# USB_Type_C_Connector_ESD.net
KiCad netlist of a schematic drawn in Altium Designer
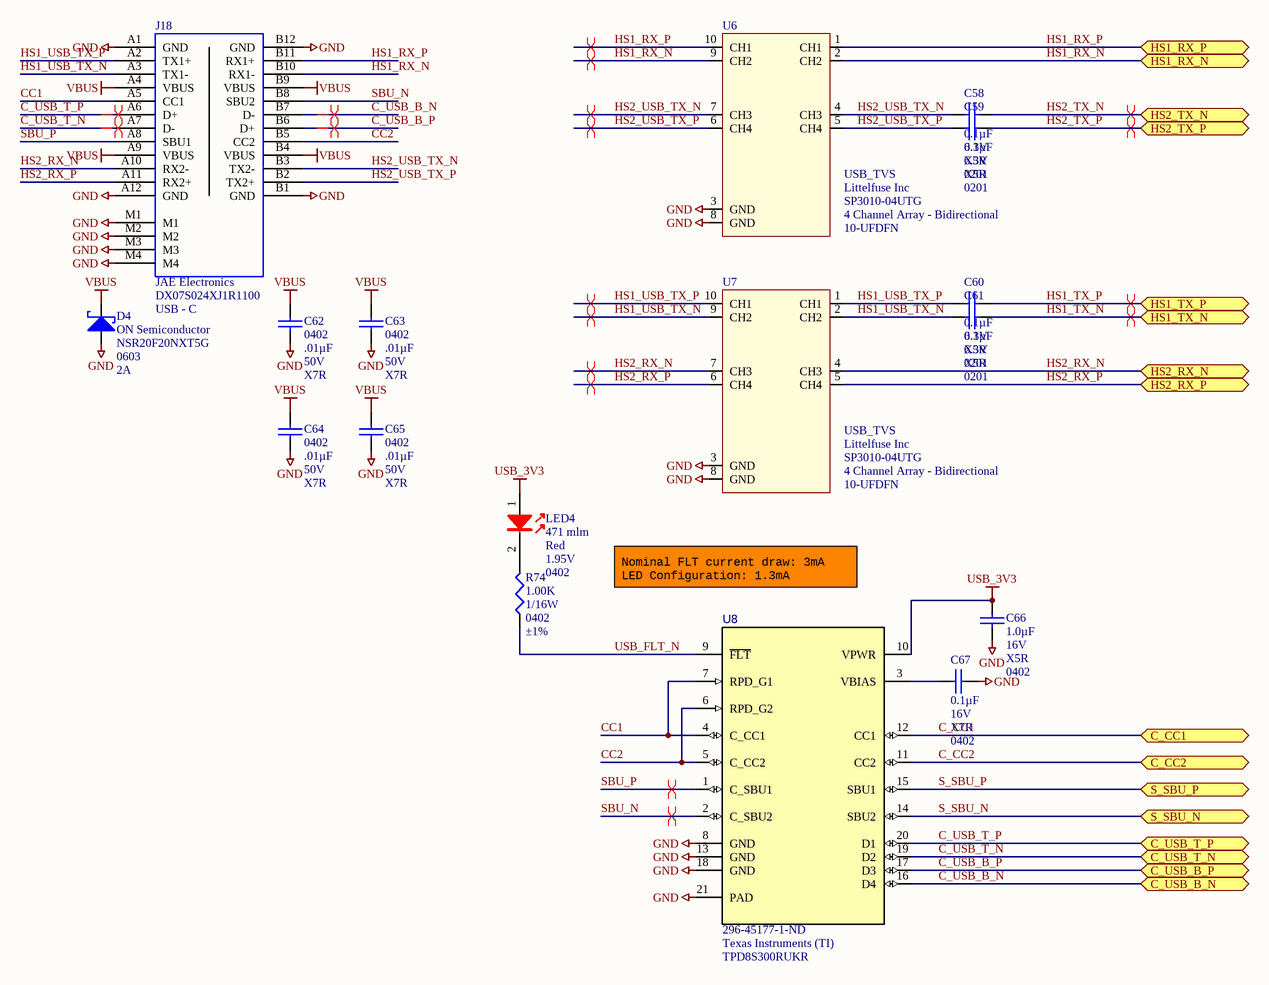
[diagram p0: USB Type C Connector ESD.SchDoc]

(export (version "E")
  (design (tool "Eeschema 10.0.6"))
  (components
    (comp (ref "C58")
      (value "0.1UF")
      (footprint "CAPC0201")
      (description "CAP CER 0.1UF 6.3V 10% X5R 0201")
      (fields
        (field (name "MANUFACTURER") "Murata Electronics North America")
        (field (name "MANUFACTURER PART NUMBER") "GRM033R60J104KE19D")
        (field (name "CAPACITANCE") "0.1µF")
        (field (name "VOLTAGE - RATED") "6.3V")
        (field (name "TEMPERATURE COEFFICIENT") "X5R")
        (field (name "PACKAGE / CASE") "0201")
      )
      (libsource (lib "Main LibraryX") (part "C_0201_0.1UF"))
    )
    (comp (ref "C59")
      (value "0.1UF")
      (footprint "CAPC0201")
      (description "CAP CER 0.1UF 6.3V 10% X5R 0201")
      (fields
        (field (name "MANUFACTURER") "Murata Electronics North America")
        (field (name "MANUFACTURER PART NUMBER") "GRM033R60J104KE19D")
        (field (name "CAPACITANCE") "0.1µF")
        (field (name "VOLTAGE - RATED") "6.3V")
        (field (name "TEMPERATURE COEFFICIENT") "X5R")
        (field (name "PACKAGE / CASE") "0201")
      )
      (libsource (lib "Main LibraryX") (part "C_0201_0.1UF"))
    )
    (comp (ref "C60")
      (value "0.1UF")
      (footprint "CAPC0201")
      (description "CAP CER 0.1UF 6.3V 10% X5R 0201")
      (fields
        (field (name "MANUFACTURER") "Murata Electronics North America")
        (field (name "MANUFACTURER PART NUMBER") "GRM033R60J104KE19D")
        (field (name "CAPACITANCE") "0.1µF")
        (field (name "VOLTAGE - RATED") "6.3V")
        (field (name "TEMPERATURE COEFFICIENT") "X5R")
        (field (name "PACKAGE / CASE") "0201")
      )
      (libsource (lib "Main LibraryX") (part "C_0201_0.1UF"))
    )
    (comp (ref "C61")
      (value "0.1UF")
      (footprint "CAPC0201")
      (description "CAP CER 0.1UF 6.3V 10% X5R 0201")
      (fields
        (field (name "MANUFACTURER") "Murata Electronics North America")
        (field (name "MANUFACTURER PART NUMBER") "GRM033R60J104KE19D")
        (field (name "CAPACITANCE") "0.1µF")
        (field (name "VOLTAGE - RATED") "6.3V")
        (field (name "TEMPERATURE COEFFICIENT") "X5R")
        (field (name "PACKAGE / CASE") "0201")
      )
      (libsource (lib "Main LibraryX") (part "C_0201_0.1UF"))
    )
    (comp (ref "C62")
      (value "10000pF")
      (footprint "C_0402")
      (description "CAP CERAMIC .01UF 50V X7R 0402")
      (fields
        (field (name "MANUFACTURER") "Murata Electronics North America")
        (field (name "MANUFACTURER PART NUMBER") "GRM155R71H103KA88D")
        (field (name "PACKAGE / CASE") "0402")
        (field (name "CAPACITANCE") ".01µF")
        (field (name "VOLTAGE - RATED") "50V")
        (field (name "TEMPERATURE COEFFICIENT") "X7R")
      )
      (libsource (lib "Main Library") (part "C_0402_10000PF_50V"))
    )
    (comp (ref "C63")
      (value "10000pF")
      (footprint "C_0402")
      (description "CAP CERAMIC .01UF 50V X7R 0402")
      (fields
        (field (name "MANUFACTURER") "Murata Electronics North America")
        (field (name "MANUFACTURER PART NUMBER") "GRM155R71H103KA88D")
        (field (name "PACKAGE / CASE") "0402")
        (field (name "CAPACITANCE") ".01µF")
        (field (name "VOLTAGE - RATED") "50V")
        (field (name "TEMPERATURE COEFFICIENT") "X7R")
      )
      (libsource (lib "Main Library") (part "C_0402_10000PF_50V"))
    )
    (comp (ref "C64")
      (value "10000pF")
      (footprint "C_0402")
      (description "CAP CERAMIC .01UF 50V X7R 0402")
      (fields
        (field (name "MANUFACTURER") "Murata Electronics North America")
        (field (name "MANUFACTURER PART NUMBER") "GRM155R71H103KA88D")
        (field (name "PACKAGE / CASE") "0402")
        (field (name "CAPACITANCE") ".01µF")
        (field (name "VOLTAGE - RATED") "50V")
        (field (name "TEMPERATURE COEFFICIENT") "X7R")
      )
      (libsource (lib "Main Library") (part "C_0402_10000PF_50V"))
    )
    (comp (ref "C65")
      (value "10000pF")
      (footprint "C_0402")
      (description "CAP CERAMIC .01UF 50V X7R 0402")
      (fields
        (field (name "MANUFACTURER") "Murata Electronics North America")
        (field (name "MANUFACTURER PART NUMBER") "GRM155R71H103KA88D")
        (field (name "PACKAGE / CASE") "0402")
        (field (name "CAPACITANCE") ".01µF")
        (field (name "VOLTAGE - RATED") "50V")
        (field (name "TEMPERATURE COEFFICIENT") "X7R")
      )
      (libsource (lib "Main Library") (part "C_0402_10000PF_50V"))
    )
    (comp (ref "C66")
      (value "1.0uF")
      (footprint "C_ERA-0402")
      (description "CAP CER 1.0UF 16V X5R 0402")
      (fields
        (field (name "MANUFACTURER") "Taiyo Yuden")
        (field (name "MANUFACTURER PART NUMBER") "EMK105BJ105KV-F")
        (field (name "CAPACITANCE") "1.0µF")
        (field (name "VOLTAGE - RATED") "16V")
        (field (name "TEMPERATURE COEFFICIENT") "X5R")
        (field (name "PACKAGE / CASE") "0402")
      )
      (libsource (lib "Main LibraryX") (part "C_0402_1.0UF_16V"))
    )
    (comp (ref "C67")
      (value "0.1uF")
      (footprint "C_0402")
      (description "CAP CER .10UF 16V X7R 0402")
      (fields
        (field (name "MANUFACTURER") "Murata Electronics North America")
        (field (name "MANUFACTURER PART NUMBER") "GRM155R71C104KA88J")
        (field (name "CAPACITANCE") "0.1µF")
        (field (name "VOLTAGE - RATED") "16V")
        (field (name "TEMPERATURE COEFFICIENT") "X7R")
        (field (name "PACKAGE / CASE") "0402")
      )
      (libsource (lib "Main LibraryX") (part "C_0402_0.1UF_16V"))
    )
    (comp (ref "D4")
      (value "D_SCHOTT_30V_2A_XDFN")
      (footprint "DSN2_0603")
      (description "DIODE SCHOTTKY 30V 2A 2DSN")
      (fields
        (field (name "MANUFACTURER") "ON Semiconductor")
        (field (name "MANUFACTURER PART NUMBER") "NSR20F20NXT5G")
        (field (name "CASE/PACKAGE") "0603")
        (field (name "AVERAGE RECTIFIED CURRENT") "2A")
      )
      (libsource (lib "Cospan Design") (part "D_SCHOTT_30V_2A_XDFN"))
    )
    (comp (ref "J18")
      (value "J_DX07S024XJ1R1100")
      (footprint "DX07S024XJ1R1100")
      (description "CONN RCPT USB C TOP MNT HYBRID")
      (fields
        (field (name "MANUFACTURER") "JAE Electronics")
        (field (name "MANUFACTURER PART NUMBER") "DX07S024XJ1R1100")
        (field (name "CONNECTOR TYPE") "USB - C")
      )
      (libsource (lib "Cospan Design") (part "J_DX07S024XJ1R1100"))
    )
    (comp (ref "LED4")
      (value "LED_RED_0402")
      (footprint "DIOM1005X07L_RED")
      (description "LED 1X0.5MM 630NM RD WTR CLR SMD")
      (fields
        (field (name "MANUFACTURER") "Kingbright Corp")
        (field (name "MANUFACTURER PART NUMBER") "APHHS1005SURCK")
        (field (name "LUMINOUS FLUX @ CURRENT - TEST") "471 mlm")
        (field (name "COLOR") "Red")
        (field (name "VOLTAGE - FORWARD (VF) TYP") "1.95V")
        (field (name "PACKAGE / CASE") "0402")
      )
      (libsource (lib "Main Library") (part "LED_RED_0402"))
    )
    (comp (ref "R74")
      (value "1.0k Ohms")
      (footprint "R_0402")
      (description "RES 1.00K OHM 1/16W 1% 0402 SMD")
      (fields
        (field (name "MANUFACTURER") "Yageo")
        (field (name "MANUFACTURER PART NUMBER") "RC0402FR-071KL")
        (field (name "RESISTANCE IN OHMS") "1.00K")
        (field (name "POWER (WATTS)") "1/16W")
        (field (name "CASE") "0402")
        (field (name "TOLERANCE") "±1%")
      )
      (libsource (lib "Main Library") (part "R_0402_1.0K"))
    )
    (comp (ref "U6")
      (value "USB_TVS")
      (footprint "TVS_DIODE_USB3.0-10")
      (description "TVS ARRAY ESD 4CH .45PF 8KV UDFN")
      (fields
        (field (name "MANUFACTURER") "Littelfuse Inc")
        (field (name "MANUFACTURER PART NUMBER") "SP3010-04UTG")
        (field (name "POLARIZATION") "4 Channel Array - Bidirectional")
        (field (name "PACKAGE / CASE") "10-UFDFN")
      )
      (libsource (lib "Main LibraryX") (part "U_SP3010-04UTG"))
    )
    (comp (ref "U7")
      (value "USB_TVS")
      (footprint "TVS_DIODE_USB3.0-10")
      (description "TVS ARRAY ESD 4CH .45PF 8KV UDFN")
      (fields
        (field (name "MANUFACTURER") "Littelfuse Inc")
        (field (name "MANUFACTURER PART NUMBER") "SP3010-04UTG")
        (field (name "POLARIZATION") "4 Channel Array - Bidirectional")
        (field (name "PACKAGE / CASE") "10-UFDFN")
      )
      (libsource (lib "Main LibraryX") (part "U_SP3010-04UTG"))
    )
    (comp (ref "U8")
      (value "U_TPD8S300RUK")
      (footprint "RUK0020B")
      (description "PRODUCTION DEVICE OF TPD8S300 US")
      (fields
        (field (name "SUPPLIER PART NUMBER 1") "296-45177-1-ND")
        (field (name "MANUFACTURER") "Texas Instruments (TI)")
        (field (name "MANUFACTURER PART NUMBER") "TPD8S300RUKR")
      )
      (libsource (lib "Cospan Design") (part "U_TPD8S300RUK"))
    )
  )
  (nets
    (net (code "1") (name "/CC1") (class "Default")
      (node (ref "J18") (pin "A5") (pinfunction "CC1_A5") (pintype "passive"))
      (node (ref "U8") (pin "4") (pinfunction "C_CC1_4") (pintype "bidirectional"))
      (node (ref "U8") (pin "7") (pinfunction "RPD_G1_7") (pintype "input"))
    )
    (net (code "2") (name "/CC2") (class "Default")
      (node (ref "J18") (pin "B5") (pinfunction "CC2_B5") (pintype "passive"))
      (node (ref "U8") (pin "5") (pinfunction "C_CC2_5") (pintype "bidirectional"))
      (node (ref "U8") (pin "6") (pinfunction "RPD_G2_6") (pintype "input"))
    )
    (net (code "3") (name "/C_CC1") (class "Default")
      (node (ref "U8") (pin "12") (pinfunction "CC1_12") (pintype "bidirectional"))
    )
    (net (code "4") (name "/C_CC2") (class "Default")
      (node (ref "U8") (pin "11") (pinfunction "CC2_11") (pintype "bidirectional"))
    )
    (net (code "5") (name "/C_USB_B_N") (class "Default")
      (node (ref "J18") (pin "B7") (pinfunction "D-_B7") (pintype "passive"))
      (node (ref "U8") (pin "16") (pinfunction "D4_16") (pintype "bidirectional"))
    )
    (net (code "6") (name "/C_USB_B_P") (class "Default")
      (node (ref "J18") (pin "B6") (pinfunction "D+_B6") (pintype "passive"))
      (node (ref "U8") (pin "17") (pinfunction "D3_17") (pintype "bidirectional"))
    )
    (net (code "7") (name "/C_USB_T_N") (class "Default")
      (node (ref "J18") (pin "A7") (pinfunction "D-_A7") (pintype "passive"))
      (node (ref "U8") (pin "19") (pinfunction "D2_19") (pintype "bidirectional"))
    )
    (net (code "8") (name "/C_USB_T_P") (class "Default")
      (node (ref "J18") (pin "A6") (pinfunction "D+_A6") (pintype "passive"))
      (node (ref "U8") (pin "20") (pinfunction "D1_20") (pintype "bidirectional"))
    )
    (net (code "9") (name "/HS1_RX_N") (class "Default")
      (node (ref "J18") (pin "B10") (pinfunction "RX1-_B10") (pintype "passive"))
      (node (ref "U6") (pin "2") (pinfunction "CH2_2") (pintype "passive"))
      (node (ref "U6") (pin "9") (pinfunction "CH2_9") (pintype "passive"))
    )
    (net (code "10") (name "/HS1_RX_P") (class "Default")
      (node (ref "J18") (pin "B11") (pinfunction "RX1+_B11") (pintype "passive"))
      (node (ref "U6") (pin "1") (pinfunction "CH1_1") (pintype "passive"))
      (node (ref "U6") (pin "10") (pinfunction "CH1_10") (pintype "passive"))
    )
    (net (code "11") (name "/HS1_TX_N") (class "Default")
      (node (ref "C61") (pin "2") (pinfunction "2_2") (pintype "passive"))
    )
    (net (code "12") (name "/HS1_TX_P") (class "Default")
      (node (ref "C60") (pin "2") (pinfunction "2_2") (pintype "passive"))
    )
    (net (code "13") (name "/HS1_USB_TX_N") (class "Default")
      (node (ref "C61") (pin "1") (pinfunction "1_1") (pintype "passive"))
      (node (ref "J18") (pin "A3") (pinfunction "TX1-_A3") (pintype "passive"))
      (node (ref "U7") (pin "2") (pinfunction "CH2_2") (pintype "passive"))
      (node (ref "U7") (pin "9") (pinfunction "CH2_9") (pintype "passive"))
    )
    (net (code "14") (name "/HS1_USB_TX_P") (class "Default")
      (node (ref "C60") (pin "1") (pinfunction "1_1") (pintype "passive"))
      (node (ref "J18") (pin "A2") (pinfunction "TX1+_A2") (pintype "passive"))
      (node (ref "U7") (pin "1") (pinfunction "CH1_1") (pintype "passive"))
      (node (ref "U7") (pin "10") (pinfunction "CH1_10") (pintype "passive"))
    )
    (net (code "15") (name "/HS2_RX_N") (class "Default")
      (node (ref "J18") (pin "A10") (pinfunction "RX2-_A10") (pintype "passive"))
      (node (ref "U7") (pin "4") (pinfunction "CH3_4") (pintype "passive"))
      (node (ref "U7") (pin "7") (pinfunction "CH3_7") (pintype "passive"))
    )
    (net (code "16") (name "/HS2_RX_P") (class "Default")
      (node (ref "J18") (pin "A11") (pinfunction "RX2+_A11") (pintype "passive"))
      (node (ref "U7") (pin "5") (pinfunction "CH4_5") (pintype "passive"))
      (node (ref "U7") (pin "6") (pinfunction "CH4_6") (pintype "passive"))
    )
    (net (code "17") (name "/HS2_TX_N") (class "Default")
      (node (ref "C58") (pin "2") (pinfunction "2_2") (pintype "passive"))
    )
    (net (code "18") (name "/HS2_TX_P") (class "Default")
      (node (ref "C59") (pin "2") (pinfunction "2_2") (pintype "passive"))
    )
    (net (code "19") (name "/HS2_USB_TX_N") (class "Default")
      (node (ref "C58") (pin "1") (pinfunction "1_1") (pintype "passive"))
      (node (ref "J18") (pin "B3") (pinfunction "TX2-_B3") (pintype "passive"))
      (node (ref "U6") (pin "4") (pinfunction "CH3_4") (pintype "passive"))
      (node (ref "U6") (pin "7") (pinfunction "CH3_7") (pintype "passive"))
    )
    (net (code "20") (name "/HS2_USB_TX_P") (class "Default")
      (node (ref "C59") (pin "1") (pinfunction "1_1") (pintype "passive"))
      (node (ref "J18") (pin "B2") (pinfunction "TX2+_B2") (pintype "passive"))
      (node (ref "U6") (pin "5") (pinfunction "CH4_5") (pintype "passive"))
      (node (ref "U6") (pin "6") (pinfunction "CH4_6") (pintype "passive"))
    )
    (net (code "21") (name "/SBU_N") (class "Default")
      (node (ref "J18") (pin "B8") (pinfunction "SBU2_B8") (pintype "passive"))
      (node (ref "U8") (pin "2") (pinfunction "C_SBU2_2") (pintype "bidirectional"))
    )
    (net (code "22") (name "/SBU_P") (class "Default")
      (node (ref "J18") (pin "A8") (pinfunction "SBU1_A8") (pintype "passive"))
      (node (ref "U8") (pin "1") (pinfunction "C_SBU1_1") (pintype "bidirectional"))
    )
    (net (code "23") (name "/S_SBU_N") (class "Default")
      (node (ref "U8") (pin "14") (pinfunction "SBU2_14") (pintype "bidirectional"))
    )
    (net (code "24") (name "/S_SBU_P") (class "Default")
      (node (ref "U8") (pin "15") (pinfunction "SBU1_15") (pintype "bidirectional"))
    )
    (net (code "25") (name "/USB_FLT_N") (class "Default")
      (node (ref "R74") (pin "2") (pinfunction "2_2") (pintype "passive"))
      (node (ref "U8") (pin "9") (pinfunction "FLT_9") (pintype "open_collector"))
    )
    (net (code "26") (name "GND") (class "Default")
      (node (ref "C62") (pin "1") (pinfunction "1_1") (pintype "passive"))
      (node (ref "C63") (pin "1") (pinfunction "1_1") (pintype "passive"))
      (node (ref "C64") (pin "1") (pinfunction "1_1") (pintype "passive"))
      (node (ref "C65") (pin "1") (pinfunction "1_1") (pintype "passive"))
      (node (ref "C66") (pin "1") (pinfunction "1_1") (pintype "passive"))
      (node (ref "C67") (pin "1") (pinfunction "1_1") (pintype "passive"))
      (node (ref "D4") (pin "2") (pinfunction "A_2") (pintype "passive"))
      (node (ref "J18") (pin "A1") (pinfunction "GND_A1") (pintype "passive"))
      (node (ref "J18") (pin "A12") (pinfunction "GND_A12") (pintype "passive"))
      (node (ref "J18") (pin "B1") (pinfunction "GND_B1") (pintype "passive"))
      (node (ref "J18") (pin "B12") (pinfunction "GND_B12") (pintype "passive"))
      (node (ref "J18") (pin "M1") (pinfunction "M1_M1") (pintype "passive"))
      (node (ref "J18") (pin "M2") (pinfunction "M2_M2") (pintype "passive"))
      (node (ref "J18") (pin "M3") (pinfunction "M3_M3") (pintype "passive"))
      (node (ref "J18") (pin "M4") (pinfunction "M4_M4") (pintype "passive"))
      (node (ref "U6") (pin "3") (pinfunction "GND_3") (pintype "passive"))
      (node (ref "U6") (pin "8") (pinfunction "GND_8") (pintype "passive"))
      (node (ref "U7") (pin "3") (pinfunction "GND_3") (pintype "passive"))
      (node (ref "U7") (pin "8") (pinfunction "GND_8") (pintype "passive"))
      (node (ref "U8") (pin "13") (pinfunction "GND_13") (pintype "power_in"))
      (node (ref "U8") (pin "18") (pinfunction "GND_18") (pintype "power_in"))
      (node (ref "U8") (pin "21") (pinfunction "PAD_21") (pintype "power_in"))
      (node (ref "U8") (pin "8") (pinfunction "GND_8") (pintype "power_in"))
    )
    (net (code "27") (name "Net-(LED4-Pad2)") (class "Default")
      (node (ref "LED4") (pin "2") (pinfunction "2_2") (pintype "passive"))
      (node (ref "R74") (pin "1") (pinfunction "1_1") (pintype "passive"))
    )
    (net (code "28") (name "Net-(U8-VBIAS)") (class "Default")
      (node (ref "C67") (pin "2") (pinfunction "2_2") (pintype "passive"))
      (node (ref "U8") (pin "3") (pinfunction "VBIAS_3") (pintype "power_in"))
    )
    (net (code "29") (name "USB_3V3") (class "Default")
      (node (ref "C66") (pin "2") (pinfunction "2_2") (pintype "passive"))
      (node (ref "LED4") (pin "1") (pinfunction "1_1") (pintype "passive"))
      (node (ref "U8") (pin "10") (pinfunction "VPWR_10") (pintype "power_in"))
    )
    (net (code "30") (name "VBUS") (class "Default")
      (node (ref "C62") (pin "2") (pinfunction "2_2") (pintype "passive"))
      (node (ref "C63") (pin "2") (pinfunction "2_2") (pintype "passive"))
      (node (ref "C64") (pin "2") (pinfunction "2_2") (pintype "passive"))
      (node (ref "C65") (pin "2") (pinfunction "2_2") (pintype "passive"))
      (node (ref "D4") (pin "1") (pinfunction "C_1") (pintype "passive"))
      (node (ref "J18") (pin "A4") (pinfunction "VBUS_A4") (pintype "passive"))
      (node (ref "J18") (pin "A9") (pinfunction "VBUS_A9") (pintype "passive"))
      (node (ref "J18") (pin "B4") (pinfunction "VBUS_B4") (pintype "passive"))
      (node (ref "J18") (pin "B9") (pinfunction "VBUS_B9") (pintype "passive"))
    )
  )
)
